# Connector.net
KiCad netlist of a schematic drawn in Altium Designer
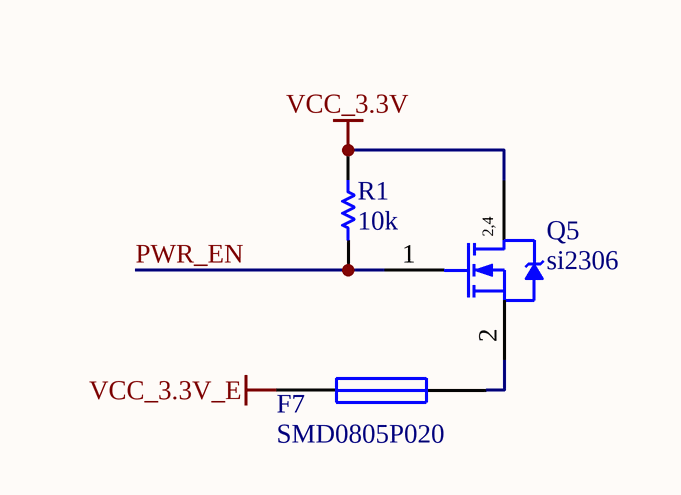
[diagram p0: Connector.SchDoc]

(export (version "E")
  (design (tool "Eeschema 10.0.6"))
  (components
    (comp (ref "F7")
      (value "SMD0805P020")
      (footprint "1206R")
      (description "Fuse")
      (fields (field (name "PUBLISHER") "Altium Limited"))
      (libsource (lib "Miscellaneous Devices") (part "Fuse 1"))
    )
    (comp (ref "Q5")
      (value "si2306")
      (footprint "SOT23-3")
      (description "BUK92150-55A")
      (fields (field (name "PUBLISHER") "Altium Limited"))
      (libsource (lib "Schlib1") (part "BUK92150-55A"))
    )
    (comp (ref "R1")
      (value "10k")
      (footprint "0603r")
      (description "Resistor")
      (fields (field (name "PUBLISHER") "Altium Limited"))
      (libsource (lib "Miscellaneous Devices") (part "Res1"))
    )
  )
  (nets
    (net (code "1") (name "/PWR_EN") (class "Default")
      (node (ref "Q5") (pin "1") (pinfunction "G_1") (pintype "passive"))
      (node (ref "R1") (pin "2") (pinfunction "2_2") (pintype "passive"))
    )
    (net (code "2") (name "Net-(Q5-S)") (class "Default")
      (node (ref "F7") (pin "2") (pinfunction "2_2") (pintype "passive"))
      (node (ref "Q5") (pin "2") (pinfunction "S_2") (pintype "passive"))
    )
    (net (code "3") (name "VCC_3.3V") (class "Default")
      (node (ref "Q5") (pin "3") (pinfunction "D_3") (pintype "passive"))
      (node (ref "R1") (pin "1") (pinfunction "1_1") (pintype "passive"))
    )
    (net (code "4") (name "VCC_3.3V_E") (class "Default")
      (node (ref "F7") (pin "1") (pinfunction "1_1") (pintype "passive"))
    )
  )
)
